# 01_-_Main.net
KiCad netlist of a schematic drawn in Altium Designer
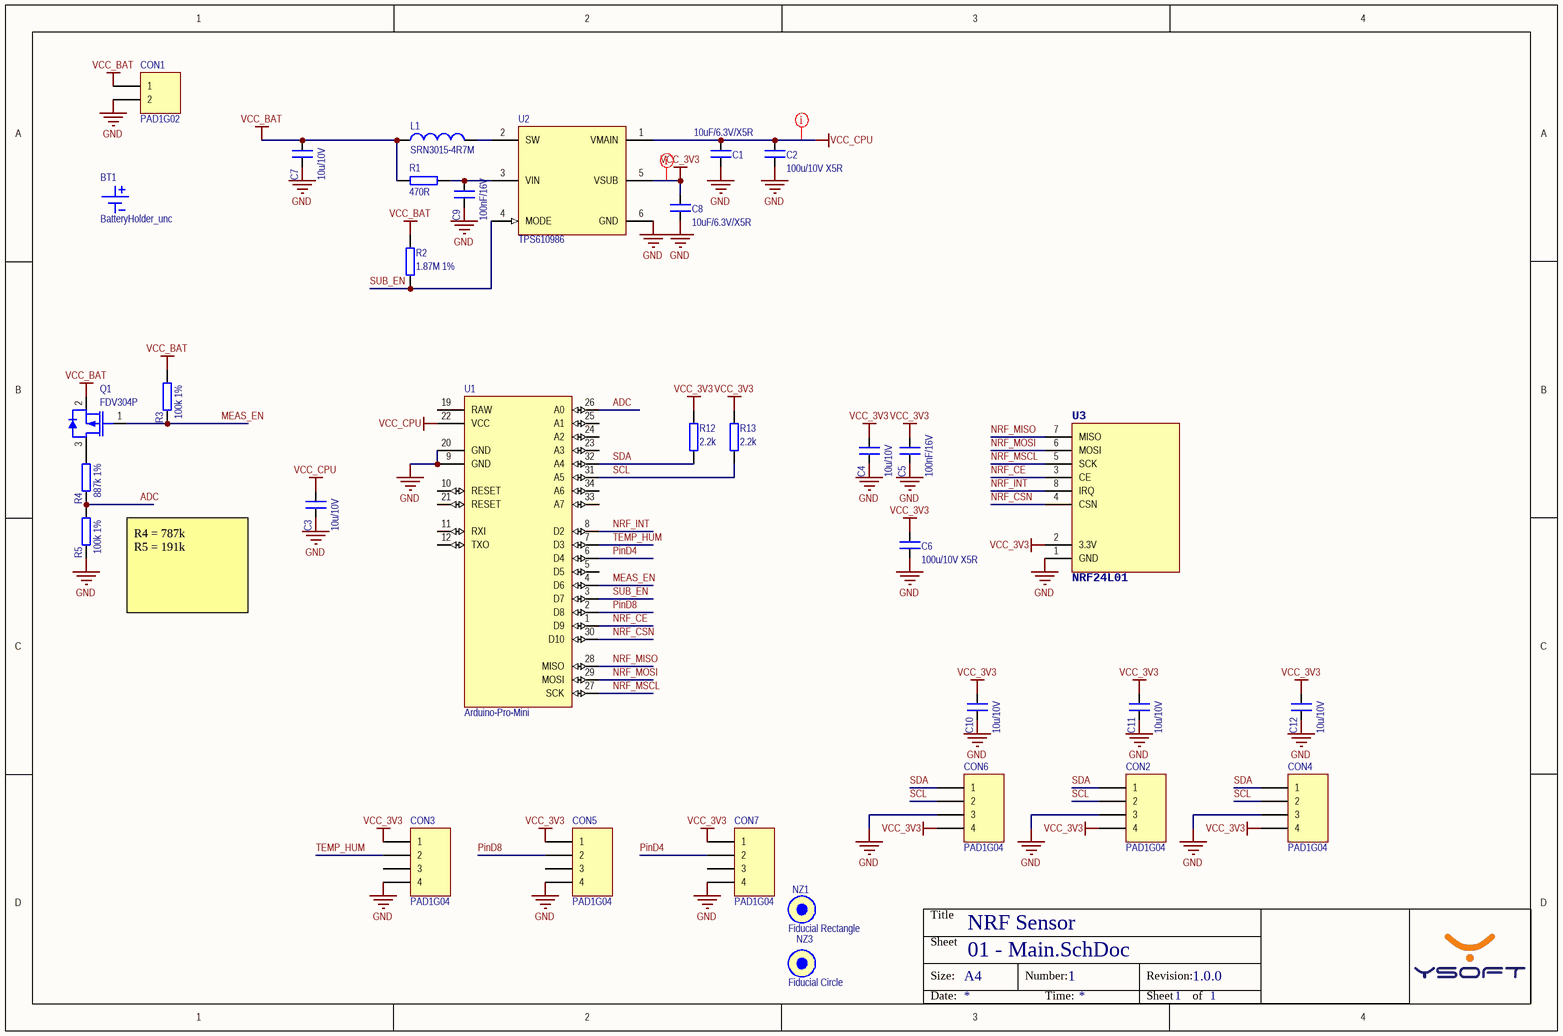
[diagram p0: 01 - Main.SchDoc]

(export (version "E")
  (design (tool "Eeschema 10.0.6"))
  (components
    (comp (ref "BT1")
      (value "BatteryHolder_unc")
      (footprint "2AAHLDR")
      (libsource (lib "Battery") (part "BatteryHoled_unc"))
    )
    (comp (ref "C1")
      (value "10uF/6.3V/X5R")
      (footprint "C-0603")
      (description "SMD Ceramic Capacitor 0603 10uF/6.3V/X5R")
      (libsource (lib "Personal Vault") (part "CapacitorNP"))
    )
    (comp (ref "C2")
      (value "100u/10V X5R")
      (footprint "C-1206")
      (description "SMD Ceramic Capacitor 1206 100u/10V X5R")
      (libsource (lib "Personal Vault") (part "CapacitorNP"))
    )
    (comp (ref "C3")
      (value "10u/10V")
      (footprint "C-0805")
      (description "SMD Ceramic Capacitor 0805 10u/10V")
      (libsource (lib "Personal Vault") (part "CapacitorNP"))
    )
    (comp (ref "C4")
      (value "10u/10V")
      (footprint "C-0805")
      (description "SMD Ceramic Capacitor 0805 10u/10V")
      (libsource (lib "Personal Vault") (part "CapacitorNP"))
    )
    (comp (ref "C5")
      (value "100nF/16V")
      (footprint "C-0603")
      (description "SMD Ceramic Capacitor 0603 100nF/16V")
      (libsource (lib "Personal Vault") (part "CapacitorNP"))
    )
    (comp (ref "C6")
      (value "100u/10V X5R")
      (footprint "C-1206")
      (description "SMD Ceramic Capacitor 1206 100u/10V X5R")
      (libsource (lib "Personal Vault") (part "CapacitorNP"))
    )
    (comp (ref "C7")
      (value "10u/10V")
      (footprint "C-0805")
      (description "SMD Ceramic Capacitor 0805 10u/10V")
      (libsource (lib "Personal Vault") (part "CapacitorNP"))
    )
    (comp (ref "C8")
      (value "10uF/6.3V/X5R")
      (footprint "C-0603")
      (description "SMD Ceramic Capacitor 0603 10uF/6.3V/X5R")
      (libsource (lib "Personal Vault") (part "CapacitorNP"))
    )
    (comp (ref "C9")
      (value "100nF/16V")
      (footprint "C-0603")
      (description "SMD Ceramic Capacitor 0603 100nF/16V")
      (libsource (lib "Personal Vault") (part "CapacitorNP"))
    )
    (comp (ref "C10")
      (value "10u/10V")
      (footprint "C-0805")
      (description "SMD Ceramic Capacitor 0805 10u/10V")
      (libsource (lib "Personal Vault") (part "CapacitorNP"))
    )
    (comp (ref "C11")
      (value "10u/10V")
      (footprint "C-0805")
      (description "SMD Ceramic Capacitor 0805 10u/10V")
      (libsource (lib "Personal Vault") (part "CapacitorNP"))
    )
    (comp (ref "C12")
      (value "10u/10V")
      (footprint "C-0805")
      (description "SMD Ceramic Capacitor 0805 10u/10V")
      (libsource (lib "Personal Vault") (part "CapacitorNP"))
    )
    (comp (ref "CON1")
      (value "PAD1G02")
      (footprint "HDR1X02S")
      (description "1x2pin single row pads, 2.54mm")
      (libsource (lib "Personal Vault") (part "Header 2"))
    )
    (comp (ref "CON2")
      (value "PAD1G04")
      (footprint "HDR1X04S")
      (description "1x4pin single row pads, 2.54mm")
      (libsource (lib "Personal Vault") (part "Header 4"))
    )
    (comp (ref "CON3")
      (value "PAD1G04")
      (footprint "HDR1X04S")
      (description "1x4pin single row pads, 2.54mm")
      (libsource (lib "Personal Vault") (part "Header 4"))
    )
    (comp (ref "CON4")
      (value "PAD1G04")
      (footprint "HDR1X04S")
      (description "1x4pin single row pads, 2.54mm")
      (libsource (lib "Personal Vault") (part "Header 4"))
    )
    (comp (ref "CON5")
      (value "PAD1G04")
      (footprint "HDR1X04S")
      (description "1x4pin single row pads, 2.54mm")
      (libsource (lib "Personal Vault") (part "Header 4"))
    )
    (comp (ref "CON6")
      (value "PAD1G04")
      (footprint "HDR1X04S")
      (description "1x4pin single row pads, 2.54mm")
      (libsource (lib "Personal Vault") (part "Header 4"))
    )
    (comp (ref "CON7")
      (value "PAD1G04")
      (footprint "HDR1X04S")
      (description "1x4pin single row pads, 2.54mm")
      (libsource (lib "Personal Vault") (part "Header 4"))
    )
    (comp (ref "L1")
      (value "SRN3015-4R7M")
      (footprint "TLU-SRN3015")
      (description "Shielded inductor 4.7uH/1.2A 3x3mm")
      (libsource (lib "Personal Vault") (part "Inductor"))
    )
    (comp (ref "NZ1")
      (value "Fiducial Rectangle")
      (footprint "Fiducial Rectangle")
      (libsource (lib "Personal Vault") (part "Fiducial Mark"))
    )
    (comp (ref "NZ3")
      (value "Fiducial Circle")
      (footprint "Fiducial Circle")
      (libsource (lib "Personal Vault") (part "Fiducial Mark"))
    )
    (comp (ref "Q1")
      (value "FDV304P")
      (footprint "SOT23-3L")
      (description "P-Channel Digital FET 25V, 460mA")
      (libsource (lib "Personal Vault") (part "P-MOSFET"))
    )
    (comp (ref "R1")
      (value "470R")
      (footprint "R-0603")
      (description "SMD Resistor 0603 470R")
      (libsource (lib "Personal Vault") (part "Resistor"))
    )
    (comp (ref "R2")
      (value "1.87M 1%")
      (footprint "R-0603")
      (description "SMD Resistor 0603 1.87M 1%")
      (libsource (lib "Personal Vault") (part "Resistor"))
    )
    (comp (ref "R3")
      (value "100k 1%")
      (footprint "R-0603")
      (description "SMD Resistor 0603 100k 1%")
      (libsource (lib "Personal Vault") (part "Resistor"))
    )
    (comp (ref "R4")
      (value "887k 1%")
      (footprint "R-0603")
      (description "SMD Resistor 0603 887k 1%")
      (libsource (lib "Personal Vault") (part "Resistor"))
    )
    (comp (ref "R5")
      (value "100k 1%")
      (footprint "R-0603")
      (description "SMD Resistor 0603 100k 1%")
      (libsource (lib "Personal Vault") (part "Resistor"))
    )
    (comp (ref "R12")
      (value "2.2k")
      (footprint "R-0603")
      (description "SMD Resistor 0603 2k2")
      (libsource (lib "Personal Vault") (part "Resistor"))
    )
    (comp (ref "R13")
      (value "2.2k")
      (footprint "R-0603")
      (description "SMD Resistor 0603 2k2")
      (libsource (lib "Personal Vault") (part "Resistor"))
    )
    (comp (ref "U1")
      (value "Arduino-Pro-Mini")
      (footprint "Arduino Mini Pro")
      (libsource (lib "Arduino") (part "Arduino-Pro-Mini"))
    )
    (comp (ref "U2")
      (value "TPS610986")
      (footprint "SON50P150X80-6N")
      (description "Ultra-Low Quiescent Current Synchronous Boost with Integrated Load Switch")
      (libsource (lib "Personal Vault") (part "TPS61098x"))
    )
    (comp (ref "U3") (value "NRF24L01") (footprint "NRF24L01") (libsource (lib "NRF") (part "NRF24L01")))
  )
  (nets
    (net (code "1") (name "/ADC") (class "Default")
      (node (ref "R4") (pin "1") (pinfunction "1_1") (pintype "passive"))
      (node (ref "R5") (pin "2") (pinfunction "2_2") (pintype "passive"))
      (node (ref "U1") (pin "26") (pinfunction "A0_26") (pintype "bidirectional"))
    )
    (net (code "2") (name "/MEAS_EN") (class "Default")
      (node (ref "Q1") (pin "1") (pinfunction "GATE_1") (pintype "passive"))
      (node (ref "R3") (pin "1") (pinfunction "1_1") (pintype "passive"))
      (node (ref "U1") (pin "4") (pinfunction "D6_4") (pintype "bidirectional"))
    )
    (net (code "3") (name "/NRF_CE") (class "Default")
      (node (ref "U1") (pin "1") (pinfunction "D9_1") (pintype "bidirectional"))
      (node (ref "U3") (pin "3") (pinfunction "CE_3") (pintype "passive"))
    )
    (net (code "4") (name "/NRF_CSN") (class "Default")
      (node (ref "U1") (pin "30") (pinfunction "D10_30") (pintype "bidirectional"))
      (node (ref "U3") (pin "4") (pinfunction "CSN_4") (pintype "passive"))
    )
    (net (code "5") (name "/NRF_INT") (class "Default")
      (node (ref "U1") (pin "8") (pinfunction "D2_8") (pintype "bidirectional"))
      (node (ref "U3") (pin "8") (pinfunction "IRQ_8") (pintype "passive"))
    )
    (net (code "6") (name "/NRF_MISO") (class "Default")
      (node (ref "U1") (pin "28") (pinfunction "MISO_28") (pintype "bidirectional"))
      (node (ref "U3") (pin "7") (pinfunction "MISO_7") (pintype "passive"))
    )
    (net (code "7") (name "/NRF_MOSI") (class "Default")
      (node (ref "U1") (pin "29") (pinfunction "MOSI_29") (pintype "bidirectional"))
      (node (ref "U3") (pin "6") (pinfunction "MOSI_6") (pintype "passive"))
    )
    (net (code "8") (name "/NRF_MSCL") (class "Default")
      (node (ref "U1") (pin "27") (pinfunction "SCK_27") (pintype "bidirectional"))
      (node (ref "U3") (pin "5") (pinfunction "SCK_5") (pintype "passive"))
    )
    (net (code "9") (name "/PinD4") (class "Default")
      (node (ref "CON7") (pin "2") (pinfunction "2_2") (pintype "passive"))
      (node (ref "U1") (pin "6") (pinfunction "D4_6") (pintype "bidirectional"))
    )
    (net (code "10") (name "/PinD8") (class "Default")
      (node (ref "CON5") (pin "2") (pinfunction "2_2") (pintype "passive"))
      (node (ref "U1") (pin "2") (pinfunction "D8_2") (pintype "bidirectional"))
    )
    (net (code "11") (name "/SCL") (class "Default")
      (node (ref "CON2") (pin "2") (pinfunction "2_2") (pintype "passive"))
      (node (ref "CON4") (pin "2") (pinfunction "2_2") (pintype "passive"))
      (node (ref "CON6") (pin "2") (pinfunction "2_2") (pintype "passive"))
      (node (ref "R13") (pin "1") (pinfunction "1_1") (pintype "passive"))
      (node (ref "U1") (pin "31") (pinfunction "A5_31") (pintype "bidirectional"))
    )
    (net (code "12") (name "/SDA") (class "Default")
      (node (ref "CON2") (pin "1") (pinfunction "1_1") (pintype "passive"))
      (node (ref "CON4") (pin "1") (pinfunction "1_1") (pintype "passive"))
      (node (ref "CON6") (pin "1") (pinfunction "1_1") (pintype "passive"))
      (node (ref "R12") (pin "1") (pinfunction "1_1") (pintype "passive"))
      (node (ref "U1") (pin "32") (pinfunction "A4_32") (pintype "bidirectional"))
    )
    (net (code "13") (name "/SUB_EN") (class "Default")
      (node (ref "R2") (pin "1") (pinfunction "1_1") (pintype "passive"))
      (node (ref "U1") (pin "3") (pinfunction "D7_3") (pintype "bidirectional"))
      (node (ref "U2") (pin "4") (pinfunction "MODE_4") (pintype "input"))
    )
    (net (code "14") (name "/TEMP_HUM") (class "Default")
      (node (ref "CON3") (pin "2") (pinfunction "2_2") (pintype "passive"))
      (node (ref "U1") (pin "7") (pinfunction "D3_7") (pintype "bidirectional"))
    )
    (net (code "15") (name "GND") (class "Default")
      (node (ref "C1") (pin "1") (pinfunction "1_1") (pintype "passive"))
      (node (ref "C10") (pin "1") (pinfunction "1_1") (pintype "passive"))
      (node (ref "C11") (pin "1") (pinfunction "1_1") (pintype "passive"))
      (node (ref "C12") (pin "1") (pinfunction "1_1") (pintype "passive"))
      (node (ref "C2") (pin "1") (pinfunction "1_1") (pintype "passive"))
      (node (ref "C3") (pin "1") (pinfunction "1_1") (pintype "passive"))
      (node (ref "C4") (pin "1") (pinfunction "1_1") (pintype "passive"))
      (node (ref "C5") (pin "1") (pinfunction "1_1") (pintype "passive"))
      (node (ref "C6") (pin "1") (pinfunction "1_1") (pintype "passive"))
      (node (ref "C7") (pin "1") (pinfunction "1_1") (pintype "passive"))
      (node (ref "C8") (pin "1") (pinfunction "1_1") (pintype "passive"))
      (node (ref "C9") (pin "1") (pinfunction "1_1") (pintype "passive"))
      (node (ref "CON1") (pin "2") (pinfunction "2_2") (pintype "passive"))
      (node (ref "CON2") (pin "3") (pinfunction "3_3") (pintype "passive"))
      (node (ref "CON3") (pin "4") (pinfunction "4_4") (pintype "passive"))
      (node (ref "CON4") (pin "3") (pinfunction "3_3") (pintype "passive"))
      (node (ref "CON5") (pin "4") (pinfunction "4_4") (pintype "passive"))
      (node (ref "CON6") (pin "3") (pinfunction "3_3") (pintype "passive"))
      (node (ref "CON7") (pin "4") (pinfunction "4_4") (pintype "passive"))
      (node (ref "R5") (pin "1") (pinfunction "1_1") (pintype "passive"))
      (node (ref "U1") (pin "20") (pinfunction "GND_20") (pintype "power_in"))
      (node (ref "U1") (pin "9") (pinfunction "GND_9") (pintype "power_in"))
      (node (ref "U2") (pin "6") (pinfunction "GND_6") (pintype "power_in"))
      (node (ref "U3") (pin "1") (pinfunction "GND_1") (pintype "power_in"))
    )
    (net (code "16") (name "Net-(Q1-DRAIN)") (class "Default")
      (node (ref "Q1") (pin "3") (pinfunction "DRAIN_3") (pintype "passive"))
      (node (ref "R4") (pin "2") (pinfunction "2_2") (pintype "passive"))
    )
    (net (code "17") (name "Net-(U2-SW)") (class "Default")
      (node (ref "L1") (pin "2") (pinfunction "2_2") (pintype "passive"))
      (node (ref "U2") (pin "2") (pinfunction "SW_2") (pintype "passive"))
    )
    (net (code "18") (name "Net-(U2-VIN)") (class "Default")
      (node (ref "C9") (pin "2") (pinfunction "2_2") (pintype "passive"))
      (node (ref "R1") (pin "2") (pinfunction "2_2") (pintype "passive"))
      (node (ref "U2") (pin "3") (pinfunction "VIN_3") (pintype "power_in"))
    )
    (net (code "19") (name "VCC_3V3") (class "Default")
      (node (ref "C10") (pin "2") (pinfunction "2_2") (pintype "passive"))
      (node (ref "C11") (pin "2") (pinfunction "2_2") (pintype "passive"))
      (node (ref "C12") (pin "2") (pinfunction "2_2") (pintype "passive"))
      (node (ref "C4") (pin "2") (pinfunction "2_2") (pintype "passive"))
      (node (ref "C5") (pin "2") (pinfunction "2_2") (pintype "passive"))
      (node (ref "C6") (pin "2") (pinfunction "2_2") (pintype "passive"))
      (node (ref "C8") (pin "2") (pinfunction "2_2") (pintype "passive"))
      (node (ref "CON2") (pin "4") (pinfunction "4_4") (pintype "passive"))
      (node (ref "CON3") (pin "1") (pinfunction "1_1") (pintype "passive"))
      (node (ref "CON4") (pin "4") (pinfunction "4_4") (pintype "passive"))
      (node (ref "CON5") (pin "1") (pinfunction "1_1") (pintype "passive"))
      (node (ref "CON6") (pin "4") (pinfunction "4_4") (pintype "passive"))
      (node (ref "CON7") (pin "1") (pinfunction "1_1") (pintype "passive"))
      (node (ref "R12") (pin "2") (pinfunction "2_2") (pintype "passive"))
      (node (ref "R13") (pin "2") (pinfunction "2_2") (pintype "passive"))
      (node (ref "U2") (pin "5") (pinfunction "VSUB_5") (pintype "passive"))
      (node (ref "U3") (pin "2") (pinfunction "3.3V_2") (pintype "power_in"))
    )
    (net (code "20") (name "VCC_BAT") (class "Default")
      (node (ref "C7") (pin "2") (pinfunction "2_2") (pintype "passive"))
      (node (ref "CON1") (pin "1") (pinfunction "1_1") (pintype "passive"))
      (node (ref "L1") (pin "1") (pinfunction "1_1") (pintype "passive"))
      (node (ref "Q1") (pin "2") (pinfunction "SOURCE_2") (pintype "passive"))
      (node (ref "R1") (pin "1") (pinfunction "1_1") (pintype "passive"))
      (node (ref "R2") (pin "2") (pinfunction "2_2") (pintype "passive"))
      (node (ref "R3") (pin "2") (pinfunction "2_2") (pintype "passive"))
    )
    (net (code "21") (name "VCC_CPU") (class "Default")
      (node (ref "C1") (pin "2") (pinfunction "2_2") (pintype "passive"))
      (node (ref "C2") (pin "2") (pinfunction "2_2") (pintype "passive"))
      (node (ref "C3") (pin "2") (pinfunction "2_2") (pintype "passive"))
      (node (ref "U1") (pin "22") (pinfunction "VCC_22") (pintype "power_in"))
      (node (ref "U2") (pin "1") (pinfunction "VMAIN_1") (pintype "passive"))
    )
    (net (code "22") (name "unconnected-(CON3-Pad3)") (class "Default")
      (node (ref "CON3") (pin "3") (pinfunction "3_3") (pintype "passive"))
    )
    (net (code "23") (name "unconnected-(CON5-Pad3)") (class "Default")
      (node (ref "CON5") (pin "3") (pinfunction "3_3") (pintype "passive"))
    )
    (net (code "24") (name "unconnected-(CON7-Pad3)") (class "Default")
      (node (ref "CON7") (pin "3") (pinfunction "3_3") (pintype "passive"))
    )
    (net (code "25") (name "unconnected-(U1-A1-Pad25)") (class "Default")
      (node (ref "U1") (pin "25") (pinfunction "A1_25") (pintype "bidirectional"))
    )
    (net (code "26") (name "unconnected-(U1-A2-Pad24)") (class "Default")
      (node (ref "U1") (pin "24") (pinfunction "A2_24") (pintype "bidirectional"))
    )
    (net (code "27") (name "unconnected-(U1-A3-Pad23)") (class "Default")
      (node (ref "U1") (pin "23") (pinfunction "A3_23") (pintype "bidirectional"))
    )
    (net (code "28") (name "unconnected-(U1-A6-Pad34)") (class "Default")
      (node (ref "U1") (pin "34") (pinfunction "A6_34") (pintype "bidirectional"))
    )
    (net (code "29") (name "unconnected-(U1-A7-Pad33)") (class "Default")
      (node (ref "U1") (pin "33") (pinfunction "A7_33") (pintype "bidirectional"))
    )
    (net (code "30") (name "unconnected-(U1-D5-Pad5)") (class "Default")
      (node (ref "U1") (pin "5") (pinfunction "D5_5") (pintype "bidirectional"))
    )
    (net (code "31") (name "unconnected-(U1-RAW-Pad19)") (class "Default")
      (node (ref "U1") (pin "19") (pinfunction "RAW_19") (pintype "power_in"))
    )
    (net (code "32") (name "unconnected-(U1-RESET-Pad10)") (class "Default")
      (node (ref "U1") (pin "10") (pinfunction "RESET_10") (pintype "bidirectional"))
    )
    (net (code "33") (name "unconnected-(U1-RESET-Pad21)") (class "Default")
      (node (ref "U1") (pin "21") (pinfunction "RESET_21") (pintype "bidirectional"))
    )
    (net (code "34") (name "unconnected-(U1-RXI-Pad11)") (class "Default")
      (node (ref "U1") (pin "11") (pinfunction "RXI_11") (pintype "bidirectional"))
    )
    (net (code "35") (name "unconnected-(U1-TXO-Pad12)") (class "Default")
      (node (ref "U1") (pin "12") (pinfunction "TXO_12") (pintype "bidirectional"))
    )
  )
)
